# CH32V003F4P6-R0-1v1.net
KiCad netlist of a schematic drawn in Altium Designer
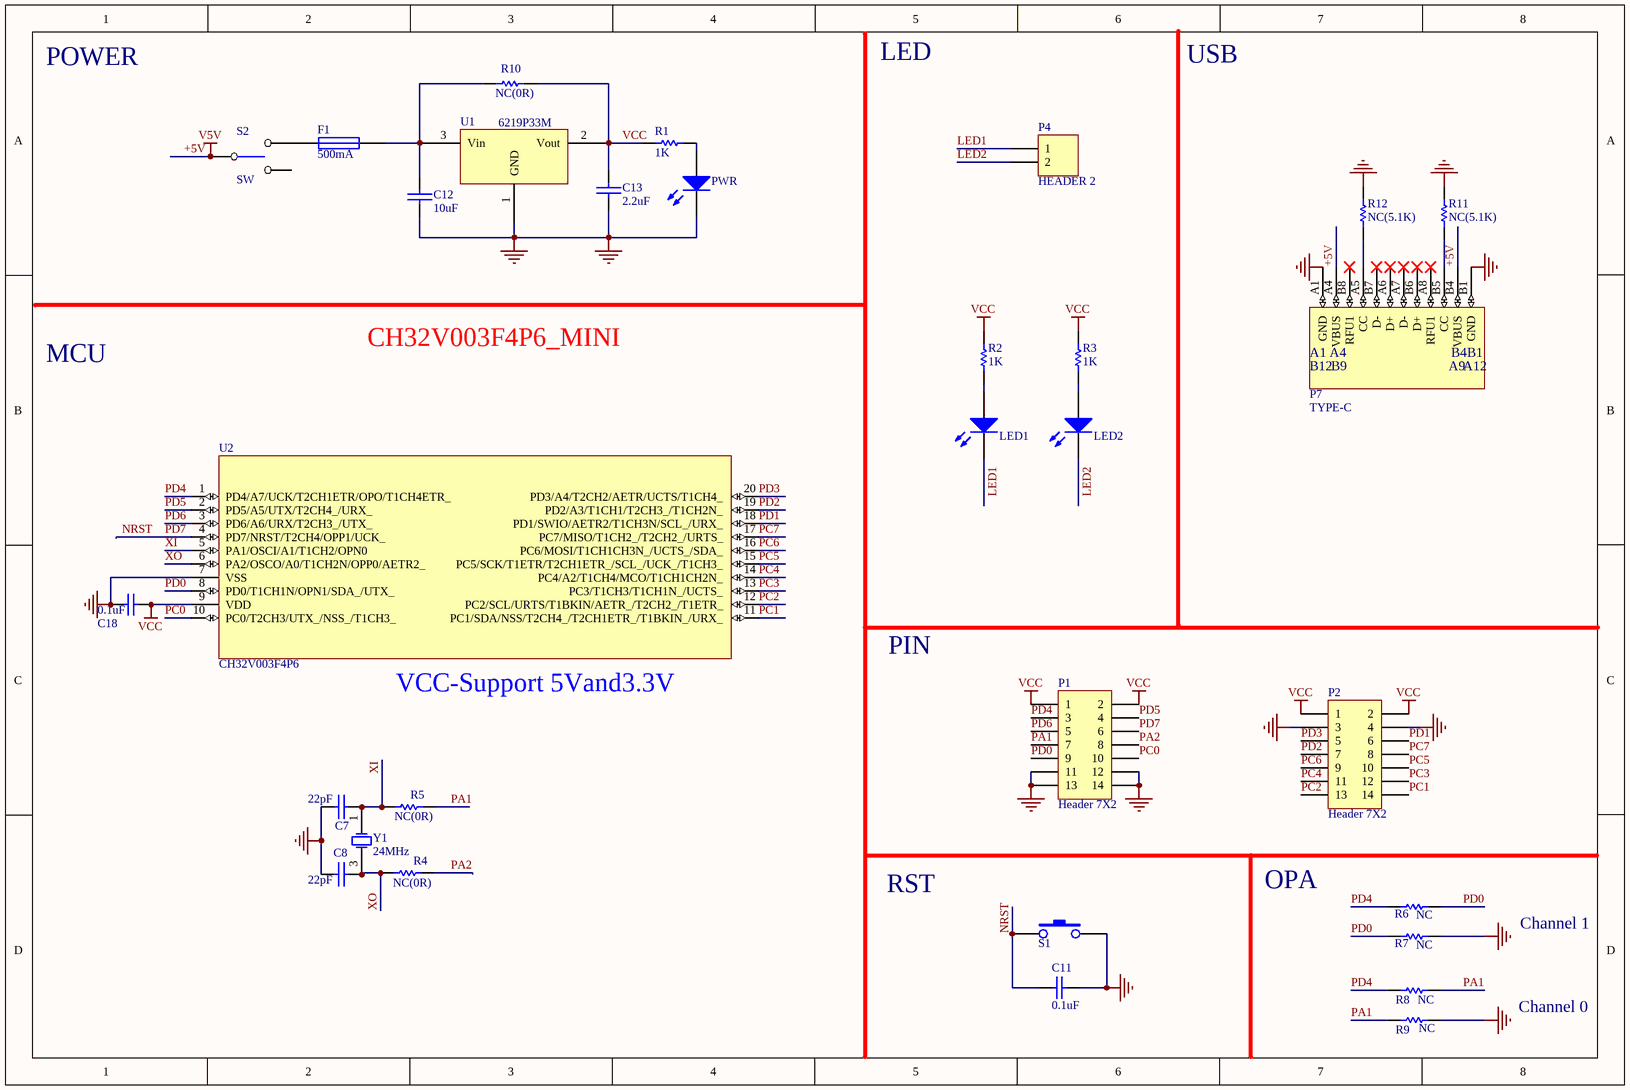
[diagram p0: CH32V003F4P6-R0-1v1.SchDoc]

(export (version "E")
  (design (tool "Eeschema 10.0.6"))
  (components
    (comp (ref "C7")
      (value "22pF")
      (footprint "0603_C")
      (description "Capacitor")
      (libsource (lib "*") (part "CAP"))
    )
    (comp (ref "C8")
      (value "22pF")
      (footprint "0603_C")
      (description "Capacitor")
      (libsource (lib "*") (part "CAP"))
    )
    (comp (ref "C11")
      (value "0.1uF")
      (footprint "0603_C")
      (description "Capacitor")
      (fields (field (name "PUBLISHER") "Altium Limited"))
      (libsource (lib "*") (part "Cap"))
    )
    (comp (ref "C12")
      (value "10uF")
      (footprint "3216_C")
      (description "Capacitor")
      (libsource (lib "wch_sch_others") (part "CAP"))
    )
    (comp (ref "C13")
      (value "2.2uF")
      (footprint "0603_C")
      (description "Capacitor")
      (libsource (lib "wch_sch_others") (part "CAP"))
    )
    (comp (ref "C18")
      (value "0.1uF")
      (footprint "0603_C")
      (description "Capacitor")
      (fields (field (name "PUBLISHER") "Altium Limited"))
      (libsource (lib "*") (part "Cap"))
    )
    (comp (ref "F1")
      (value "500mA")
      (footprint "0603")
      (description "Fuse")
      (libsource (lib "*") (part "FUSE1"))
    )
    (comp (ref "LED1")
      (value "LED1   blue")
      (footprint "0603+")
      (description "Typical INFRARED GaAs LED")
      (fields (field (name "PUBLISHER") "Altium Limited"))
      (libsource (lib "") (part "LED0_1"))
    )
    (comp (ref "LED2")
      (value "LED2  blue")
      (footprint "0603+")
      (description "Typical INFRARED GaAs LED")
      (fields (field (name "PUBLISHER") "Altium Limited"))
      (libsource (lib "") (part "LED0_1"))
    )
    (comp (ref "P1")
      (value "Header 7X2")
      (footprint "IDC14-2.54mm")
      (description "Header, 7-Pin, Dual row")
      (fields (field (name "PUBLISHER") "Altium Limited"))
      (libsource (lib "Miscellaneous Connectors") (part "Header 7X2"))
    )
    (comp (ref "P2")
      (value "Header 7X2")
      (footprint "IDC14-2.54mm")
      (description "Header, 7-Pin, Dual row")
      (fields (field (name "PUBLISHER") "Altium Limited"))
      (libsource (lib "Miscellaneous Connectors") (part "Header 7X2"))
    )
    (comp (ref "P4")
      (value "HEADER 2")
      (footprint "MYPCB:SIP2-2.54mm")
      (description "Header, 2-Pin")
      (libsource (lib "wch_sch_others") (part "HEADER 2"))
    )
    (comp (ref "P7")
      (value "TYPE-C")
      (footprint "TYPE-C-Receptacle-2.0")
      (libsource (lib "*") (part "TYPE-C1"))
    )
    (comp (ref "PWR")
      (value "POWER  red")
      (footprint "0603+")
      (description "Typical INFRARED GaAs LED")
      (fields (field (name "PUBLISHER") "Altium Limited"))
      (libsource (lib "*") (part "LED0"))
    )
    (comp (ref "R1")
      (value "1K")
      (footprint "0603")
      (description "Semiconductor Resistor")
      (fields (field (name "PUBLISHER") "Altium Limited"))
      (libsource (lib "*") (part "Res Semi"))
    )
    (comp (ref "R2")
      (value "1K")
      (footprint "0603")
      (description "Semiconductor Resistor")
      (fields (field (name "PUBLISHER") "Altium Limited"))
      (libsource (lib "*") (part "Res Semi"))
    )
    (comp (ref "R3")
      (value "1K")
      (footprint "0603")
      (description "Semiconductor Resistor")
      (fields (field (name "PUBLISHER") "Altium Limited"))
      (libsource (lib "*") (part "Res Semi"))
    )
    (comp (ref "R4")
      (value "NC(0R)")
      (footprint "0603")
      (description "Semiconductor Resistor")
      (fields (field (name "Comment") "0R") (field (name "PUBLISHER") "Altium Limited"))
      (libsource (lib "*") (part "Res Semi"))
    )
    (comp (ref "R5")
      (value "NC(0R)")
      (footprint "0603")
      (description "Semiconductor Resistor")
      (fields (field (name "Comment") "0R") (field (name "PUBLISHER") "Altium Limited"))
      (libsource (lib "*") (part "Res Semi"))
    )
    (comp (ref "R6")
      (value "NC")
      (footprint "0603")
      (description "Semiconductor Resistor")
      (fields (field (name "Comment") "0R") (field (name "PUBLISHER") "Altium Limited"))
      (libsource (lib "*") (part "Res Semi"))
    )
    (comp (ref "R7")
      (value "NC")
      (footprint "0603")
      (description "Semiconductor Resistor")
      (fields (field (name "Comment") "0R") (field (name "PUBLISHER") "Altium Limited"))
      (libsource (lib "*") (part "Res Semi"))
    )
    (comp (ref "R8")
      (value "NC")
      (footprint "0603")
      (description "Semiconductor Resistor")
      (fields (field (name "Comment") "0R") (field (name "PUBLISHER") "Altium Limited"))
      (libsource (lib "*") (part "Res Semi"))
    )
    (comp (ref "R9")
      (value "NC")
      (footprint "0603")
      (description "Semiconductor Resistor")
      (fields (field (name "Comment") "0R") (field (name "PUBLISHER") "Altium Limited"))
      (libsource (lib "*") (part "Res Semi"))
    )
    (comp (ref "R10")
      (value "NC(0R)")
      (footprint "0603")
      (description "Semiconductor Resistor")
      (fields (field (name "Comment") "0R") (field (name "PUBLISHER") "Altium Limited"))
      (libsource (lib "*") (part "Res Semi"))
    )
    (comp (ref "R11")
      (value "NC(5.1K)")
      (footprint "0603")
      (description "Semiconductor Resistor")
      (fields (field (name "Comment") "0R") (field (name "PUBLISHER") "Altium Limited"))
      (libsource (lib "*") (part "Res Semi"))
    )
    (comp (ref "R12")
      (value "NC(5.1K)")
      (footprint "0603")
      (description "Semiconductor Resistor")
      (fields (field (name "Comment") "0R") (field (name "PUBLISHER") "Altium Limited"))
      (libsource (lib "*") (part "Res Semi"))
    )
    (comp (ref "S1") (value "NRST") (footprint "SMD_6.1x3.65x2.5mm-KEY") (libsource (lib "*") (part "KEY")))
    (comp (ref "S2") (value "SW") (footprint "SW1") (libsource (lib "*") (part "SW")))
    (comp (ref "U1")
      (value "6219P33M")
      (footprint "SOT-23")
      (libsource (lib "wch_sch_others") (part "6219P33M"))
    )
    (comp (ref "U2")
      (value "CH32V003F4P6")
      (footprint "TSSOP20")
      (description "RISC-V MCU, 48MHz")
      (libsource (lib "CHXXX") (part "CH32V003F4P6"))
    )
    (comp (ref "Y1")
      (value "24MHz")
      (footprint "XT3225")
      (description "Crystal Oscillator")
      (fields (field (name "PUBLISHER") "Altium Limited"))
      (libsource (lib "*") (part "XTAL"))
    )
  )
  (nets
    (net (code "1") (name "/LED1") (class "Default")
      (node (ref "LED1") (pin "2") (pinfunction "K_2") (pintype "passive"))
      (node (ref "P4") (pin "1") (pinfunction "1_1") (pintype "passive"))
    )
    (net (code "2") (name "/LED2") (class "Default")
      (node (ref "LED2") (pin "2") (pinfunction "K_2") (pintype "passive"))
      (node (ref "P4") (pin "2") (pinfunction "2_2") (pintype "passive"))
    )
    (net (code "3") (name "/NRST") (class "Default")
      (node (ref "C11") (pin "2") (pinfunction "2_2") (pintype "passive"))
      (node (ref "P1") (pin "6") (pinfunction "6_6") (pintype "passive"))
      (node (ref "S1") (pin "1") (pinfunction "1_1") (pintype "passive"))
      (node (ref "U2") (pin "4") (pinfunction "PD7/NRST/T2CH4/OPP1/UCK__4") (pintype "bidirectional"))
    )
    (net (code "4") (name "/PA1") (class "Default")
      (node (ref "P1") (pin "7") (pinfunction "7_7") (pintype "passive"))
      (node (ref "R5") (pin "2") (pinfunction "2_2") (pintype "passive"))
      (node (ref "R8") (pin "2") (pinfunction "2_2") (pintype "passive"))
      (node (ref "R9") (pin "1") (pinfunction "1_1") (pintype "passive"))
    )
    (net (code "5") (name "/PA2") (class "Default")
      (node (ref "P1") (pin "8") (pinfunction "8_8") (pintype "passive"))
      (node (ref "R4") (pin "2") (pinfunction "2_2") (pintype "passive"))
    )
    (net (code "6") (name "/PC0") (class "Default")
      (node (ref "P1") (pin "10") (pinfunction "10_10") (pintype "passive"))
      (node (ref "U2") (pin "10") (pinfunction "PC0/T2CH3/UTX_/NSS_/T1CH3__10") (pintype "bidirectional"))
    )
    (net (code "7") (name "/PC1") (class "Default")
      (node (ref "P2") (pin "14") (pinfunction "14_14") (pintype "passive"))
      (node (ref "U2") (pin "11") (pinfunction "PC1/SDA/NSS/T2CH4_/T2CH1ETR_/T1BKIN_/URX__11") (pintype "bidirectional"))
    )
    (net (code "8") (name "/PC2") (class "Default")
      (node (ref "P2") (pin "13") (pinfunction "13_13") (pintype "passive"))
      (node (ref "U2") (pin "12") (pinfunction "PC2/SCL/URTS/T1BKIN/AETR_/T2CH2_/T1ETR__12") (pintype "bidirectional"))
    )
    (net (code "9") (name "/PC3") (class "Default")
      (node (ref "P2") (pin "12") (pinfunction "12_12") (pintype "passive"))
      (node (ref "U2") (pin "13") (pinfunction "PC3/T1CH3/T1CH1N_/UCTS__13") (pintype "bidirectional"))
    )
    (net (code "10") (name "/PC4") (class "Default")
      (node (ref "P2") (pin "11") (pinfunction "11_11") (pintype "passive"))
      (node (ref "U2") (pin "14") (pinfunction "PC4/A2/T1CH4/MCO/T1CH1CH2N__14") (pintype "bidirectional"))
    )
    (net (code "11") (name "/PC5") (class "Default")
      (node (ref "P2") (pin "10") (pinfunction "10_10") (pintype "passive"))
      (node (ref "U2") (pin "15") (pinfunction "PC5/SCK/T1ETR/T2CH1ETR_/SCL_/UCK_/T1CH3__15") (pintype "bidirectional"))
    )
    (net (code "12") (name "/PC6") (class "Default")
      (node (ref "P2") (pin "9") (pinfunction "9_9") (pintype "passive"))
      (node (ref "U2") (pin "16") (pinfunction "PC6/MOSI/T1CH1CH3N_/UCTS_/SDA__16") (pintype "bidirectional"))
    )
    (net (code "13") (name "/PC7") (class "Default")
      (node (ref "P2") (pin "8") (pinfunction "8_8") (pintype "passive"))
      (node (ref "U2") (pin "17") (pinfunction "PC7/MISO/T1CH2_/T2CH2_/URTS__17") (pintype "bidirectional"))
    )
    (net (code "14") (name "/PD0") (class "Default")
      (node (ref "P1") (pin "9") (pinfunction "9_9") (pintype "passive"))
      (node (ref "R6") (pin "2") (pinfunction "2_2") (pintype "passive"))
      (node (ref "R7") (pin "1") (pinfunction "1_1") (pintype "passive"))
      (node (ref "U2") (pin "8") (pinfunction "PD0/T1CH1N/OPN1/SDA_/UTX__8") (pintype "bidirectional"))
    )
    (net (code "15") (name "/PD1") (class "Default")
      (node (ref "P2") (pin "6") (pinfunction "6_6") (pintype "passive"))
      (node (ref "U2") (pin "18") (pinfunction "PD1/SWIO/AETR2/T1CH3N/SCL_/URX__18") (pintype "bidirectional"))
    )
    (net (code "16") (name "/PD2") (class "Default")
      (node (ref "P2") (pin "7") (pinfunction "7_7") (pintype "passive"))
      (node (ref "U2") (pin "19") (pinfunction "PD2/A3/T1CH1/T2CH3_/T1CH2N__19") (pintype "bidirectional"))
    )
    (net (code "17") (name "/PD3") (class "Default")
      (node (ref "P2") (pin "5") (pinfunction "5_5") (pintype "passive"))
      (node (ref "U2") (pin "20") (pinfunction "PD3/A4/T2CH2/AETR/UCTS/T1CH4__20") (pintype "bidirectional"))
    )
    (net (code "18") (name "/PD4") (class "Default")
      (node (ref "P1") (pin "3") (pinfunction "3_3") (pintype "passive"))
      (node (ref "R6") (pin "1") (pinfunction "1_1") (pintype "passive"))
      (node (ref "R8") (pin "1") (pinfunction "1_1") (pintype "passive"))
      (node (ref "U2") (pin "1") (pinfunction "PD4/A7/UCK/T2CH1ETR/OPO/T1CH4ETR__1") (pintype "bidirectional"))
    )
    (net (code "19") (name "/PD5") (class "Default")
      (node (ref "P1") (pin "4") (pinfunction "4_4") (pintype "passive"))
      (node (ref "U2") (pin "2") (pinfunction "PD5/A5/UTX/T2CH4_/URX__2") (pintype "bidirectional"))
    )
    (net (code "20") (name "/PD6") (class "Default")
      (node (ref "P1") (pin "5") (pinfunction "5_5") (pintype "passive"))
      (node (ref "U2") (pin "3") (pinfunction "PD6/A6/URX/T2CH3_/UTX__3") (pintype "bidirectional"))
    )
    (net (code "21") (name "/XI") (class "Default")
      (node (ref "C7") (pin "2") (pinfunction "2_2") (pintype "passive"))
      (node (ref "R5") (pin "1") (pinfunction "1_1") (pintype "passive"))
      (node (ref "U2") (pin "5") (pinfunction "PA1/OSCI/A1/T1CH2/OPN0_5") (pintype "bidirectional"))
      (node (ref "Y1") (pin "1") (pinfunction "OSC1_1") (pintype "passive"))
    )
    (net (code "22") (name "/XO") (class "Default")
      (node (ref "C8") (pin "2") (pinfunction "2_2") (pintype "passive"))
      (node (ref "R4") (pin "1") (pinfunction "1_1") (pintype "passive"))
      (node (ref "U2") (pin "6") (pinfunction "PA2/OSCO/A0/T1CH2N/OPP0/AETR2__6") (pintype "bidirectional"))
      (node (ref "Y1") (pin "3") (pinfunction "OSC2_3") (pintype "passive"))
    )
    (net (code "23") (name "GND") (class "Default")
      (node (ref "C11") (pin "1") (pinfunction "1_1") (pintype "passive"))
      (node (ref "C12") (pin "2") (pinfunction "2_2") (pintype "passive"))
      (node (ref "C13") (pin "1") (pinfunction "1_1") (pintype "passive"))
      (node (ref "C18") (pin "1") (pinfunction "1_1") (pintype "passive"))
      (node (ref "C7") (pin "1") (pinfunction "1_1") (pintype "passive"))
      (node (ref "C8") (pin "1") (pinfunction "1_1") (pintype "passive"))
      (node (ref "P1") (pin "11") (pinfunction "11_11") (pintype "passive"))
      (node (ref "P1") (pin "12") (pinfunction "12_12") (pintype "passive"))
      (node (ref "P1") (pin "13") (pinfunction "13_13") (pintype "passive"))
      (node (ref "P1") (pin "14") (pinfunction "14_14") (pintype "passive"))
      (node (ref "P2") (pin "3") (pinfunction "3_3") (pintype "passive"))
      (node (ref "P2") (pin "4") (pinfunction "4_4") (pintype "passive"))
      (node (ref "P7") (pin "A1") (pinfunction "GND_A1") (pintype "bidirectional"))
      (node (ref "P7") (pin "B1") (pinfunction "GND_B1") (pintype "bidirectional"))
      (node (ref "PWR") (pin "2") (pinfunction "K_2") (pintype "passive"))
      (node (ref "R11") (pin "2") (pinfunction "2_2") (pintype "passive"))
      (node (ref "R12") (pin "2") (pinfunction "2_2") (pintype "passive"))
      (node (ref "R7") (pin "2") (pinfunction "2_2") (pintype "passive"))
      (node (ref "R9") (pin "2") (pinfunction "2_2") (pintype "passive"))
      (node (ref "S1") (pin "2") (pinfunction "2_2") (pintype "passive"))
      (node (ref "U1") (pin "1") (pinfunction "GND_1") (pintype "passive"))
      (node (ref "U2") (pin "7") (pinfunction "VSS_7") (pintype "power_in"))
    )
    (net (code "24") (name "Net-(F1-Pad1)") (class "Default")
      (node (ref "F1") (pin "1") (pinfunction "1_1") (pintype "passive"))
      (node (ref "S2") (pin "3") (pinfunction "3_3") (pintype "passive"))
    )
    (net (code "25") (name "Net-(LED1-A)") (class "Default")
      (node (ref "LED1") (pin "1") (pinfunction "A_1") (pintype "passive"))
      (node (ref "R2") (pin "2") (pinfunction "2_2") (pintype "passive"))
    )
    (net (code "26") (name "Net-(LED2-A)") (class "Default")
      (node (ref "LED2") (pin "1") (pinfunction "A_1") (pintype "passive"))
      (node (ref "R3") (pin "2") (pinfunction "2_2") (pintype "passive"))
    )
    (net (code "27") (name "Net-(P7-CC-PadA5)") (class "Default")
      (node (ref "P7") (pin "A5") (pinfunction "CC_A5") (pintype "bidirectional"))
      (node (ref "R12") (pin "1") (pinfunction "1_1") (pintype "passive"))
    )
    (net (code "28") (name "Net-(P7-CC-PadB5)") (class "Default")
      (node (ref "P7") (pin "B5") (pinfunction "CC_B5") (pintype "bidirectional"))
      (node (ref "R11") (pin "1") (pinfunction "1_1") (pintype "passive"))
    )
    (net (code "29") (name "Net-(PWR-A)") (class "Default")
      (node (ref "PWR") (pin "1") (pinfunction "A_1") (pintype "passive"))
      (node (ref "R1") (pin "1") (pinfunction "1_1") (pintype "passive"))
    )
    (net (code "30") (name "Net-(U1-Vin)") (class "Default")
      (node (ref "C12") (pin "1") (pinfunction "1_1") (pintype "passive"))
      (node (ref "F1") (pin "2") (pinfunction "2_2") (pintype "passive"))
      (node (ref "R10") (pin "1") (pinfunction "1_1") (pintype "passive"))
      (node (ref "U1") (pin "3") (pinfunction "Vin_3") (pintype "passive"))
    )
    (net (code "31") (name "V5V") (class "Default")
      (node (ref "P7") (pin "A4") (pinfunction "VBUS_A4") (pintype "bidirectional"))
      (node (ref "P7") (pin "B4") (pinfunction "VBUS_B4") (pintype "bidirectional"))
      (node (ref "S2") (pin "1") (pinfunction "1_1") (pintype "passive"))
    )
    (net (code "32") (name "VCC") (class "Default")
      (node (ref "C13") (pin "2") (pinfunction "2_2") (pintype "passive"))
      (node (ref "C18") (pin "2") (pinfunction "2_2") (pintype "passive"))
      (node (ref "P1") (pin "1") (pinfunction "1_1") (pintype "passive"))
      (node (ref "P1") (pin "2") (pinfunction "2_2") (pintype "passive"))
      (node (ref "P2") (pin "1") (pinfunction "1_1") (pintype "passive"))
      (node (ref "P2") (pin "2") (pinfunction "2_2") (pintype "passive"))
      (node (ref "R1") (pin "2") (pinfunction "2_2") (pintype "passive"))
      (node (ref "R10") (pin "2") (pinfunction "2_2") (pintype "passive"))
      (node (ref "R2") (pin "1") (pinfunction "1_1") (pintype "passive"))
      (node (ref "R3") (pin "1") (pinfunction "1_1") (pintype "passive"))
      (node (ref "U1") (pin "2") (pinfunction "Vout_2") (pintype "passive"))
      (node (ref "U2") (pin "9") (pinfunction "VDD_9") (pintype "power_in"))
    )
    (net (code "33") (name "unconnected-(P7-D+-PadA6)") (class "Default")
      (node (ref "P7") (pin "A6") (pinfunction "D+_A6") (pintype "bidirectional+no_connect"))
    )
    (net (code "34") (name "unconnected-(P7-D+-PadB6)") (class "Default")
      (node (ref "P7") (pin "B6") (pinfunction "D+_B6") (pintype "bidirectional+no_connect"))
    )
    (net (code "35") (name "unconnected-(P7-D--PadA7)") (class "Default")
      (node (ref "P7") (pin "A7") (pinfunction "D-_A7") (pintype "bidirectional+no_connect"))
    )
    (net (code "36") (name "unconnected-(P7-D--PadB7)") (class "Default")
      (node (ref "P7") (pin "B7") (pinfunction "D-_B7") (pintype "bidirectional+no_connect"))
    )
    (net (code "37") (name "unconnected-(P7-RFU1-PadA8)") (class "Default")
      (node (ref "P7") (pin "A8") (pinfunction "RFU1_A8") (pintype "bidirectional+no_connect"))
    )
    (net (code "38") (name "unconnected-(P7-RFU1-PadB8)") (class "Default")
      (node (ref "P7") (pin "B8") (pinfunction "RFU1_B8") (pintype "bidirectional+no_connect"))
    )
    (net (code "39") (name "unconnected-(S2-Pad2)") (class "Default")
      (node (ref "S2") (pin "2") (pinfunction "2_2") (pintype "passive"))
    )
  )
)
